# SCH_Smart_Parking_IoT_2023-05-22.net
KiCad netlist of a schematic drawn in EasyEDA
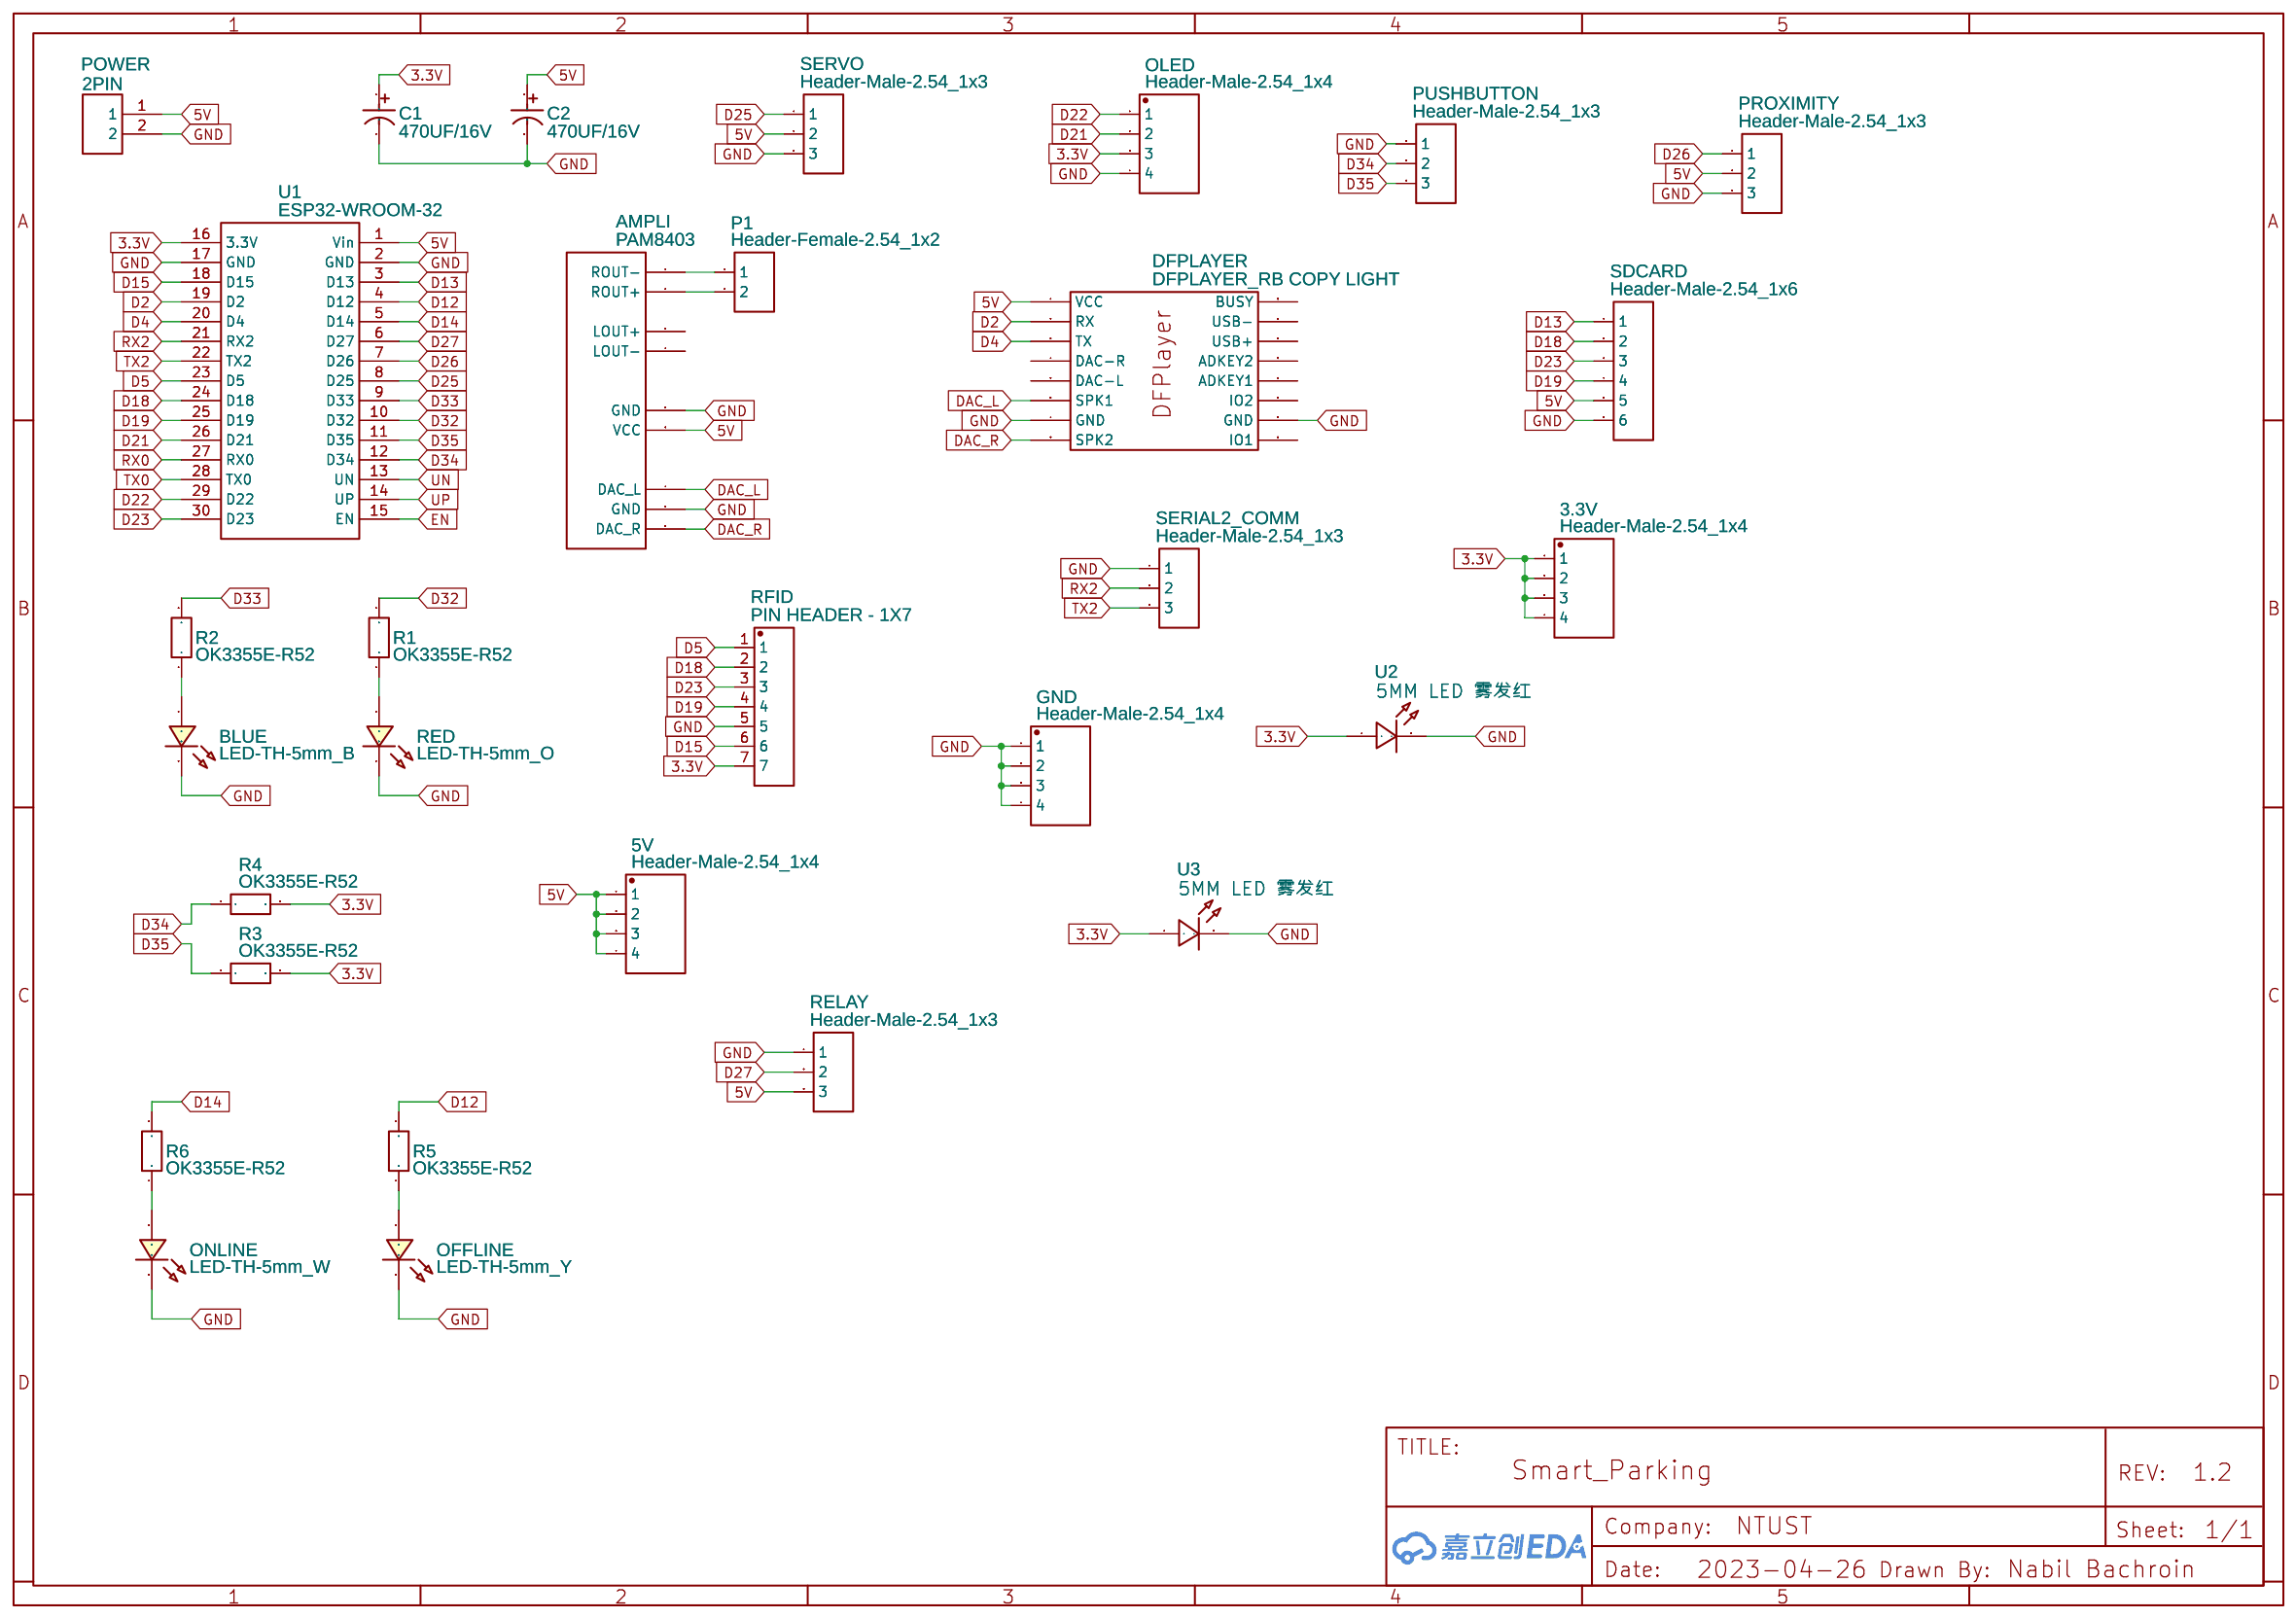
[diagram p0: schematic sheet]

(export (version "E")
  (design (tool "Eeschema 10.0.6"))
  (components
    (comp (ref "3.3V")
      (value "Header-Male-2.54_1x4")
      (fields
        (field (name "BOM_Manufacturer Part") "B-2100S04P-A110")
        (field (name "BOM_Supplier Part") "C124378")
      )
      (libsource (lib "") (part "Header-Male-2.54_1x4_3"))
    )
    (comp (ref "5V")
      (value "Header-Male-2.54_1x4")
      (fields
        (field (name "BOM_Manufacturer Part") "B-2100S04P-A110")
        (field (name "BOM_Supplier Part") "C124378")
      )
      (libsource (lib "") (part "Header-Male-2.54_1x4_1"))
    )
    (comp (ref "AMPLI") (value "PAM8403") (libsource (lib "") (part "PAM8403")))
    (comp (ref "BLUE") (value "LED-TH-5mm_B") (libsource (lib "") (part "LED-TH-5mm_B")))
    (comp (ref "C1")
      (value "470UF/16V")
      (fields
        (field (name "BOM_Manufacturer Part") "470uF/16V")
        (field (name "BOM_Supplier Part") "C9900008131")
      )
      (libsource (lib "") (part "470UF/16V"))
    )
    (comp (ref "C2")
      (value "470UF/16V")
      (fields
        (field (name "BOM_Manufacturer Part") "470uF/16V")
        (field (name "BOM_Supplier Part") "C9900008131")
      )
      (libsource (lib "") (part "470UF/16V"))
    )
    (comp (ref "DFPLAYER")
      (value "DFPLAYER_RB COPY LIGHT")
      (fields (field (name "BOM_Manufacturer Part") "DFPLAYER"))
      (libsource (lib "") (part "DFPLAYER_RB COPY LIGHT"))
    )
    (comp (ref "GND")
      (value "Header-Male-2.54_1x4")
      (fields
        (field (name "BOM_Manufacturer Part") "B-2100S04P-A110")
        (field (name "BOM_Supplier Part") "C124378")
      )
      (libsource (lib "") (part "Header-Male-2.54_1x4"))
    )
    (comp (ref "OFFLINE") (value "LED-TH-5mm_Y") (libsource (lib "") (part "LED-TH-5mm_Y")))
    (comp (ref "OLED")
      (value "Header-Male-2.54_1x4")
      (fields
        (field (name "BOM_Manufacturer Part") "B-2100S04P-A110")
        (field (name "BOM_Supplier Part") "C124378")
      )
      (libsource (lib "") (part "Header-Male-2.54_1x4_2"))
    )
    (comp (ref "ONLINE") (value "LED-TH-5mm_W") (libsource (lib "") (part "LED-TH-5mm_W")))
    (comp (ref "P1")
      (value "Header-Female-2.54_1x2")
      (fields (field (name "BOM_Manufacturer Part") "2.54-1*2P母") (field (name "BOM_Supplier Part") "C49661"))
      (libsource (lib "") (part "Header-Female-2.54_1x2"))
    )
    (comp (ref "POWER")
      (value "2PIN")
      (fields (field (name "BOM_Manufacturer Part") "Pin_Header_2"))
      (libsource (lib "") (part "2PIN"))
    )
    (comp (ref "PROXIMITY")
      (value "Header-Male-2.54_1x3")
      (fields (field (name "BOM_Manufacturer Part") "2.54-1*3P针") (field (name "BOM_Supplier Part") "C49257"))
      (libsource (lib "") (part "Header-Male-2.54_1x3"))
    )
    (comp (ref "PUSHBUTTON")
      (value "Header-Male-2.54_1x3")
      (fields (field (name "BOM_Manufacturer Part") "2.54-1*3P针") (field (name "BOM_Supplier Part") "C49257"))
      (libsource (lib "") (part "Header-Male-2.54_1x3_1"))
    )
    (comp (ref "R1")
      (value "OK3355E-R52")
      (fields (field (name "BOM_Supplier Part") "C3522642"))
      (libsource (lib "") (part "OK3355E-R52"))
    )
    (comp (ref "R2")
      (value "OK3355E-R52")
      (fields (field (name "BOM_Supplier Part") "C3522642"))
      (libsource (lib "") (part "OK3355E-R52"))
    )
    (comp (ref "R3")
      (value "OK3355E-R52")
      (fields (field (name "BOM_Supplier Part") "C3522642"))
      (libsource (lib "") (part "OK3355E-R52_1"))
    )
    (comp (ref "R4")
      (value "OK3355E-R52")
      (fields (field (name "BOM_Supplier Part") "C3522642"))
      (libsource (lib "") (part "OK3355E-R52_1"))
    )
    (comp (ref "R5")
      (value "OK3355E-R52")
      (fields (field (name "BOM_Supplier Part") "C3522642"))
      (libsource (lib "") (part "OK3355E-R52"))
    )
    (comp (ref "R6")
      (value "OK3355E-R52")
      (fields (field (name "BOM_Supplier Part") "C3522642"))
      (libsource (lib "") (part "OK3355E-R52"))
    )
    (comp (ref "RED") (value "LED-TH-5mm_O") (libsource (lib "") (part "LED-TH-5mm_O")))
    (comp (ref "RELAY")
      (value "Header-Male-2.54_1x3")
      (fields (field (name "BOM_Manufacturer Part") "2.54-1*3P针") (field (name "BOM_Supplier Part") "C49257"))
      (libsource (lib "") (part "Header-Male-2.54_1x3_3"))
    )
    (comp (ref "RFID") (value "PIN HEADER - 1X7") (libsource (lib "") (part "PIN HEADER - 1X7")))
    (comp (ref "SDCARD")
      (value "Header-Male-2.54_1x6")
      (fields
        (field (name "BOM_Manufacturer Part") "2.54-1x6P直针")
        (field (name "BOM_Supplier Part") "C37208")
      )
      (libsource (lib "") (part "Header-Male-2.54_1x6"))
    )
    (comp (ref "SERIAL2_COMM")
      (value "Header-Male-2.54_1x3")
      (fields (field (name "BOM_Manufacturer Part") "2.54-1*3P针") (field (name "BOM_Supplier Part") "C49257"))
      (libsource (lib "") (part "Header-Male-2.54_1x3_4"))
    )
    (comp (ref "SERVO")
      (value "Header-Male-2.54_1x3")
      (fields (field (name "BOM_Manufacturer Part") "2.54-1*3P针") (field (name "BOM_Supplier Part") "C49257"))
      (libsource (lib "") (part "Header-Male-2.54_1x3_2"))
    )
    (comp (ref "U1") (value "ESP32-WROOM-32") (libsource (lib "") (part "ESP32-WROOM-32")))
    (comp (ref "U2")
      (value "5MM LED 雾发红")
      (fields
        (field (name "BOM_Manufacturer Part") "5mm LED 雾发红")
        (field (name "BOM_Supplier Part") "C9900034380")
      )
      (libsource (lib "") (part "5MM LED 雾发红"))
    )
    (comp (ref "U3")
      (value "5MM LED 雾发红")
      (fields
        (field (name "BOM_Manufacturer Part") "5mm LED 雾发红")
        (field (name "BOM_Supplier Part") "C9900034380")
      )
      (libsource (lib "") (part "5MM LED 雾发红"))
    )
  )
  (nets
    (net (code "1") (name "3.3V") (class "Default")
      (node (ref "3.3V") (pin "1") (pinfunction "1_1") (pintype "unspecified"))
      (node (ref "3.3V") (pin "2") (pinfunction "2_2") (pintype "unspecified"))
      (node (ref "3.3V") (pin "3") (pinfunction "3_3") (pintype "unspecified"))
      (node (ref "3.3V") (pin "4") (pinfunction "4_4") (pintype "unspecified"))
      (node (ref "C1") (pin "1") (pinfunction "1_1") (pintype "input"))
      (node (ref "OLED") (pin "3") (pinfunction "3_3") (pintype "unspecified"))
      (node (ref "R3") (pin "2") (pinfunction "2_2") (pintype "unspecified"))
      (node (ref "R4") (pin "2") (pinfunction "2_2") (pintype "unspecified"))
      (node (ref "RFID") (pin "7") (pinfunction "7_7") (pintype "unspecified"))
      (node (ref "U1") (pin "16") (pinfunction "3.3V_16") (pintype "unspecified"))
      (node (ref "U2") (pin "1") (pinfunction "+_1") (pintype "unspecified"))
      (node (ref "U3") (pin "1") (pinfunction "+_1") (pintype "unspecified"))
    )
    (net (code "2") (name "5V") (class "Default")
      (node (ref "5V") (pin "1") (pinfunction "1_1") (pintype "unspecified"))
      (node (ref "5V") (pin "2") (pinfunction "2_2") (pintype "unspecified"))
      (node (ref "5V") (pin "3") (pinfunction "3_3") (pintype "unspecified"))
      (node (ref "5V") (pin "4") (pinfunction "4_4") (pintype "unspecified"))
      (node (ref "AMPLI") (pin "6") (pinfunction "VCC_6") (pintype "unspecified"))
      (node (ref "C2") (pin "1") (pinfunction "1_1") (pintype "input"))
      (node (ref "DFPLAYER") (pin "1") (pinfunction "VCC_1") (pintype "unspecified"))
      (node (ref "POWER") (pin "1") (pinfunction "1_1") (pintype "unspecified"))
      (node (ref "PROXIMITY") (pin "2") (pinfunction "2_2") (pintype "input"))
      (node (ref "RELAY") (pin "3") (pinfunction "3_3") (pintype "input"))
      (node (ref "SDCARD") (pin "5") (pinfunction "5_5") (pintype "input"))
      (node (ref "SERVO") (pin "2") (pinfunction "2_2") (pintype "input"))
      (node (ref "U1") (pin "1") (pinfunction "Vin_1") (pintype "unspecified"))
    )
    (net (code "3") (name "D2") (class "Default")
      (node (ref "DFPLAYER") (pin "2") (pinfunction "RX_2") (pintype "unspecified"))
      (node (ref "U1") (pin "19") (pinfunction "D2_19") (pintype "unspecified"))
    )
    (net (code "4") (name "D4") (class "Default")
      (node (ref "DFPLAYER") (pin "3") (pinfunction "TX_3") (pintype "unspecified"))
      (node (ref "U1") (pin "20") (pinfunction "D4_20") (pintype "unspecified"))
    )
    (net (code "5") (name "D5") (class "Default")
      (node (ref "RFID") (pin "1") (pinfunction "1_1") (pintype "unspecified"))
      (node (ref "U1") (pin "23") (pinfunction "D5_23") (pintype "unspecified"))
    )
    (net (code "6") (name "D12") (class "Default")
      (node (ref "R5") (pin "2") (pinfunction "2_2") (pintype "unspecified"))
      (node (ref "U1") (pin "4") (pinfunction "D12_4") (pintype "unspecified"))
    )
    (net (code "7") (name "D13") (class "Default")
      (node (ref "SDCARD") (pin "1") (pinfunction "1_1") (pintype "input"))
      (node (ref "U1") (pin "3") (pinfunction "D13_3") (pintype "unspecified"))
    )
    (net (code "8") (name "D14") (class "Default")
      (node (ref "R6") (pin "2") (pinfunction "2_2") (pintype "unspecified"))
      (node (ref "U1") (pin "5") (pinfunction "D14_5") (pintype "unspecified"))
    )
    (net (code "9") (name "D15") (class "Default")
      (node (ref "RFID") (pin "6") (pinfunction "6_6") (pintype "unspecified"))
      (node (ref "U1") (pin "18") (pinfunction "D15_18") (pintype "unspecified"))
    )
    (net (code "10") (name "D18") (class "Default")
      (node (ref "RFID") (pin "2") (pinfunction "2_2") (pintype "unspecified"))
      (node (ref "SDCARD") (pin "2") (pinfunction "2_2") (pintype "input"))
      (node (ref "U1") (pin "24") (pinfunction "D18_24") (pintype "unspecified"))
    )
    (net (code "11") (name "D19") (class "Default")
      (node (ref "RFID") (pin "4") (pinfunction "4_4") (pintype "unspecified"))
      (node (ref "SDCARD") (pin "4") (pinfunction "4_4") (pintype "input"))
      (node (ref "U1") (pin "25") (pinfunction "D19_25") (pintype "unspecified"))
    )
    (net (code "12") (name "D21") (class "Default")
      (node (ref "OLED") (pin "2") (pinfunction "2_2") (pintype "unspecified"))
      (node (ref "U1") (pin "26") (pinfunction "D21_26") (pintype "unspecified"))
    )
    (net (code "13") (name "D22") (class "Default")
      (node (ref "OLED") (pin "1") (pinfunction "1_1") (pintype "unspecified"))
      (node (ref "U1") (pin "29") (pinfunction "D22_29") (pintype "unspecified"))
    )
    (net (code "14") (name "D23") (class "Default")
      (node (ref "RFID") (pin "3") (pinfunction "3_3") (pintype "unspecified"))
      (node (ref "SDCARD") (pin "3") (pinfunction "3_3") (pintype "input"))
      (node (ref "U1") (pin "30") (pinfunction "D23_30") (pintype "unspecified"))
    )
    (net (code "15") (name "D25") (class "Default")
      (node (ref "SERVO") (pin "1") (pinfunction "1_1") (pintype "input"))
      (node (ref "U1") (pin "8") (pinfunction "D25_8") (pintype "unspecified"))
    )
    (net (code "16") (name "D26") (class "Default")
      (node (ref "PROXIMITY") (pin "1") (pinfunction "1_1") (pintype "input"))
      (node (ref "U1") (pin "7") (pinfunction "D26_7") (pintype "unspecified"))
    )
    (net (code "17") (name "D27") (class "Default")
      (node (ref "RELAY") (pin "2") (pinfunction "2_2") (pintype "input"))
      (node (ref "U1") (pin "6") (pinfunction "D27_6") (pintype "unspecified"))
    )
    (net (code "18") (name "D32") (class "Default")
      (node (ref "R1") (pin "2") (pinfunction "2_2") (pintype "unspecified"))
      (node (ref "U1") (pin "10") (pinfunction "D32_10") (pintype "unspecified"))
    )
    (net (code "19") (name "D33") (class "Default")
      (node (ref "R2") (pin "2") (pinfunction "2_2") (pintype "unspecified"))
      (node (ref "U1") (pin "9") (pinfunction "D33_9") (pintype "unspecified"))
    )
    (net (code "20") (name "D34") (class "Default")
      (node (ref "PUSHBUTTON") (pin "2") (pinfunction "2_2") (pintype "input"))
      (node (ref "R4") (pin "1") (pinfunction "1_1") (pintype "unspecified"))
      (node (ref "U1") (pin "12") (pinfunction "D34_12") (pintype "unspecified"))
    )
    (net (code "21") (name "D35") (class "Default")
      (node (ref "PUSHBUTTON") (pin "3") (pinfunction "3_3") (pintype "input"))
      (node (ref "R3") (pin "1") (pinfunction "1_1") (pintype "unspecified"))
      (node (ref "U1") (pin "11") (pinfunction "D35_11") (pintype "unspecified"))
    )
    (net (code "22") (name "DAC_L") (class "Default")
      (node (ref "AMPLI") (pin "7") (pinfunction "DAC_L_7") (pintype "unspecified"))
      (node (ref "DFPLAYER") (pin "6") (pinfunction "SPK1_6") (pintype "unspecified"))
    )
    (net (code "23") (name "DAC_R") (class "Default")
      (node (ref "AMPLI") (pin "9") (pinfunction "DAC_R_9") (pintype "unspecified"))
      (node (ref "DFPLAYER") (pin "8") (pinfunction "SPK2_8") (pintype "unspecified"))
    )
    (net (code "24") (name "EN") (class "Default")
      (node (ref "U1") (pin "15") (pinfunction "EN_15") (pintype "unspecified"))
    )
    (net (code "25") (name "GND") (class "Default")
      (node (ref "AMPLI") (pin "5") (pinfunction "GND_5") (pintype "unspecified"))
      (node (ref "AMPLI") (pin "8") (pinfunction "GND_8") (pintype "unspecified"))
      (node (ref "BLUE") (pin "2") (pinfunction "2_2") (pintype "unspecified"))
      (node (ref "C1") (pin "2") (pinfunction "2_2") (pintype "input"))
      (node (ref "C2") (pin "2") (pinfunction "2_2") (pintype "input"))
      (node (ref "DFPLAYER") (pin "10") (pinfunction "GND_10") (pintype "unspecified"))
      (node (ref "DFPLAYER") (pin "7") (pinfunction "GND_7") (pintype "unspecified"))
      (node (ref "GND") (pin "1") (pinfunction "1_1") (pintype "unspecified"))
      (node (ref "GND") (pin "2") (pinfunction "2_2") (pintype "unspecified"))
      (node (ref "GND") (pin "3") (pinfunction "3_3") (pintype "unspecified"))
      (node (ref "GND") (pin "4") (pinfunction "4_4") (pintype "unspecified"))
      (node (ref "OFFLINE") (pin "2") (pinfunction "2_2") (pintype "unspecified"))
      (node (ref "OLED") (pin "4") (pinfunction "4_4") (pintype "unspecified"))
      (node (ref "ONLINE") (pin "2") (pinfunction "2_2") (pintype "unspecified"))
      (node (ref "POWER") (pin "2") (pinfunction "2_2") (pintype "unspecified"))
      (node (ref "PROXIMITY") (pin "3") (pinfunction "3_3") (pintype "input"))
      (node (ref "PUSHBUTTON") (pin "1") (pinfunction "1_1") (pintype "input"))
      (node (ref "RED") (pin "2") (pinfunction "2_2") (pintype "unspecified"))
      (node (ref "RELAY") (pin "1") (pinfunction "1_1") (pintype "input"))
      (node (ref "RFID") (pin "5") (pinfunction "5_5") (pintype "unspecified"))
      (node (ref "SDCARD") (pin "6") (pinfunction "6_6") (pintype "input"))
      (node (ref "SERIAL2_COMM") (pin "1") (pinfunction "1_1") (pintype "input"))
      (node (ref "SERVO") (pin "3") (pinfunction "3_3") (pintype "input"))
      (node (ref "U1") (pin "17") (pinfunction "GND_17") (pintype "unspecified"))
      (node (ref "U1") (pin "2") (pinfunction "GND_2") (pintype "unspecified"))
      (node (ref "U2") (pin "2") (pinfunction "-_2") (pintype "unspecified"))
      (node (ref "U3") (pin "2") (pinfunction "-_2") (pintype "unspecified"))
    )
    (net (code "26") (name "Net-(AMPLI-ROUT+)") (class "Default")
      (node (ref "AMPLI") (pin "2") (pinfunction "ROUT+_2") (pintype "unspecified"))
      (node (ref "P1") (pin "2") (pinfunction "2_2") (pintype "input"))
    )
    (net (code "27") (name "Net-(AMPLI-ROUT-)") (class "Default")
      (node (ref "AMPLI") (pin "1") (pinfunction "ROUT-_1") (pintype "unspecified"))
      (node (ref "P1") (pin "1") (pinfunction "1_1") (pintype "input"))
    )
    (net (code "28") (name "Net-(BLUE-Pad1)") (class "Default")
      (node (ref "BLUE") (pin "1") (pinfunction "1_1") (pintype "unspecified"))
      (node (ref "R2") (pin "1") (pinfunction "1_1") (pintype "unspecified"))
    )
    (net (code "29") (name "Net-(OFFLINE-Pad1)") (class "Default")
      (node (ref "OFFLINE") (pin "1") (pinfunction "1_1") (pintype "unspecified"))
      (node (ref "R5") (pin "1") (pinfunction "1_1") (pintype "unspecified"))
    )
    (net (code "30") (name "Net-(ONLINE-Pad1)") (class "Default")
      (node (ref "ONLINE") (pin "1") (pinfunction "1_1") (pintype "unspecified"))
      (node (ref "R6") (pin "1") (pinfunction "1_1") (pintype "unspecified"))
    )
    (net (code "31") (name "Net-(R1-Pad1)") (class "Default")
      (node (ref "R1") (pin "1") (pinfunction "1_1") (pintype "unspecified"))
      (node (ref "RED") (pin "1") (pinfunction "1_1") (pintype "unspecified"))
    )
    (net (code "32") (name "RX0") (class "Default")
      (node (ref "U1") (pin "27") (pinfunction "RX0_27") (pintype "unspecified"))
    )
    (net (code "33") (name "RX2") (class "Default")
      (node (ref "SERIAL2_COMM") (pin "2") (pinfunction "2_2") (pintype "input"))
      (node (ref "U1") (pin "21") (pinfunction "RX2_21") (pintype "unspecified"))
    )
    (net (code "34") (name "TX0") (class "Default")
      (node (ref "U1") (pin "28") (pinfunction "TX0_28") (pintype "unspecified"))
    )
    (net (code "35") (name "TX2") (class "Default")
      (node (ref "SERIAL2_COMM") (pin "3") (pinfunction "3_3") (pintype "input"))
      (node (ref "U1") (pin "22") (pinfunction "TX2_22") (pintype "unspecified"))
    )
    (net (code "36") (name "UN") (class "Default")
      (node (ref "U1") (pin "13") (pinfunction "UN_13") (pintype "unspecified"))
    )
    (net (code "37") (name "UP") (class "Default")
      (node (ref "U1") (pin "14") (pinfunction "UP_14") (pintype "unspecified"))
    )
    (net (code "38") (name "unconnected-(AMPLI-LOUT+-Pad3)") (class "Default")
      (node (ref "AMPLI") (pin "3") (pinfunction "LOUT+_3") (pintype "unspecified"))
    )
    (net (code "39") (name "unconnected-(AMPLI-LOUT--Pad4)") (class "Default")
      (node (ref "AMPLI") (pin "4") (pinfunction "LOUT-_4") (pintype "unspecified"))
    )
    (net (code "40") (name "unconnected-(DFPLAYER-ADKEY1-Pad12)") (class "Default")
      (node (ref "DFPLAYER") (pin "12") (pinfunction "ADKEY1_12") (pintype "unspecified"))
    )
    (net (code "41") (name "unconnected-(DFPLAYER-ADKEY2-Pad13)") (class "Default")
      (node (ref "DFPLAYER") (pin "13") (pinfunction "ADKEY2_13") (pintype "unspecified"))
    )
    (net (code "42") (name "unconnected-(DFPLAYER-BUSY-Pad16)") (class "Default")
      (node (ref "DFPLAYER") (pin "16") (pinfunction "BUSY_16") (pintype "unspecified"))
    )
    (net (code "43") (name "unconnected-(DFPLAYER-DAC-L-Pad5)") (class "Default")
      (node (ref "DFPLAYER") (pin "5") (pinfunction "DAC-L_5") (pintype "unspecified"))
    )
    (net (code "44") (name "unconnected-(DFPLAYER-DAC-R-Pad4)") (class "Default")
      (node (ref "DFPLAYER") (pin "4") (pinfunction "DAC-R_4") (pintype "unspecified"))
    )
    (net (code "45") (name "unconnected-(DFPLAYER-IO1-Pad9)") (class "Default")
      (node (ref "DFPLAYER") (pin "9") (pinfunction "IO1_9") (pintype "unspecified"))
    )
    (net (code "46") (name "unconnected-(DFPLAYER-IO2-Pad11)") (class "Default")
      (node (ref "DFPLAYER") (pin "11") (pinfunction "IO2_11") (pintype "unspecified"))
    )
    (net (code "47") (name "unconnected-(DFPLAYER-USB+-Pad14)") (class "Default")
      (node (ref "DFPLAYER") (pin "14") (pinfunction "USB+_14") (pintype "unspecified"))
    )
    (net (code "48") (name "unconnected-(DFPLAYER-USB--Pad15)") (class "Default")
      (node (ref "DFPLAYER") (pin "15") (pinfunction "USB-_15") (pintype "unspecified"))
    )
  )
)
